# DIO_RJ45.net
KiCad netlist of a schematic drawn in Altium Designer
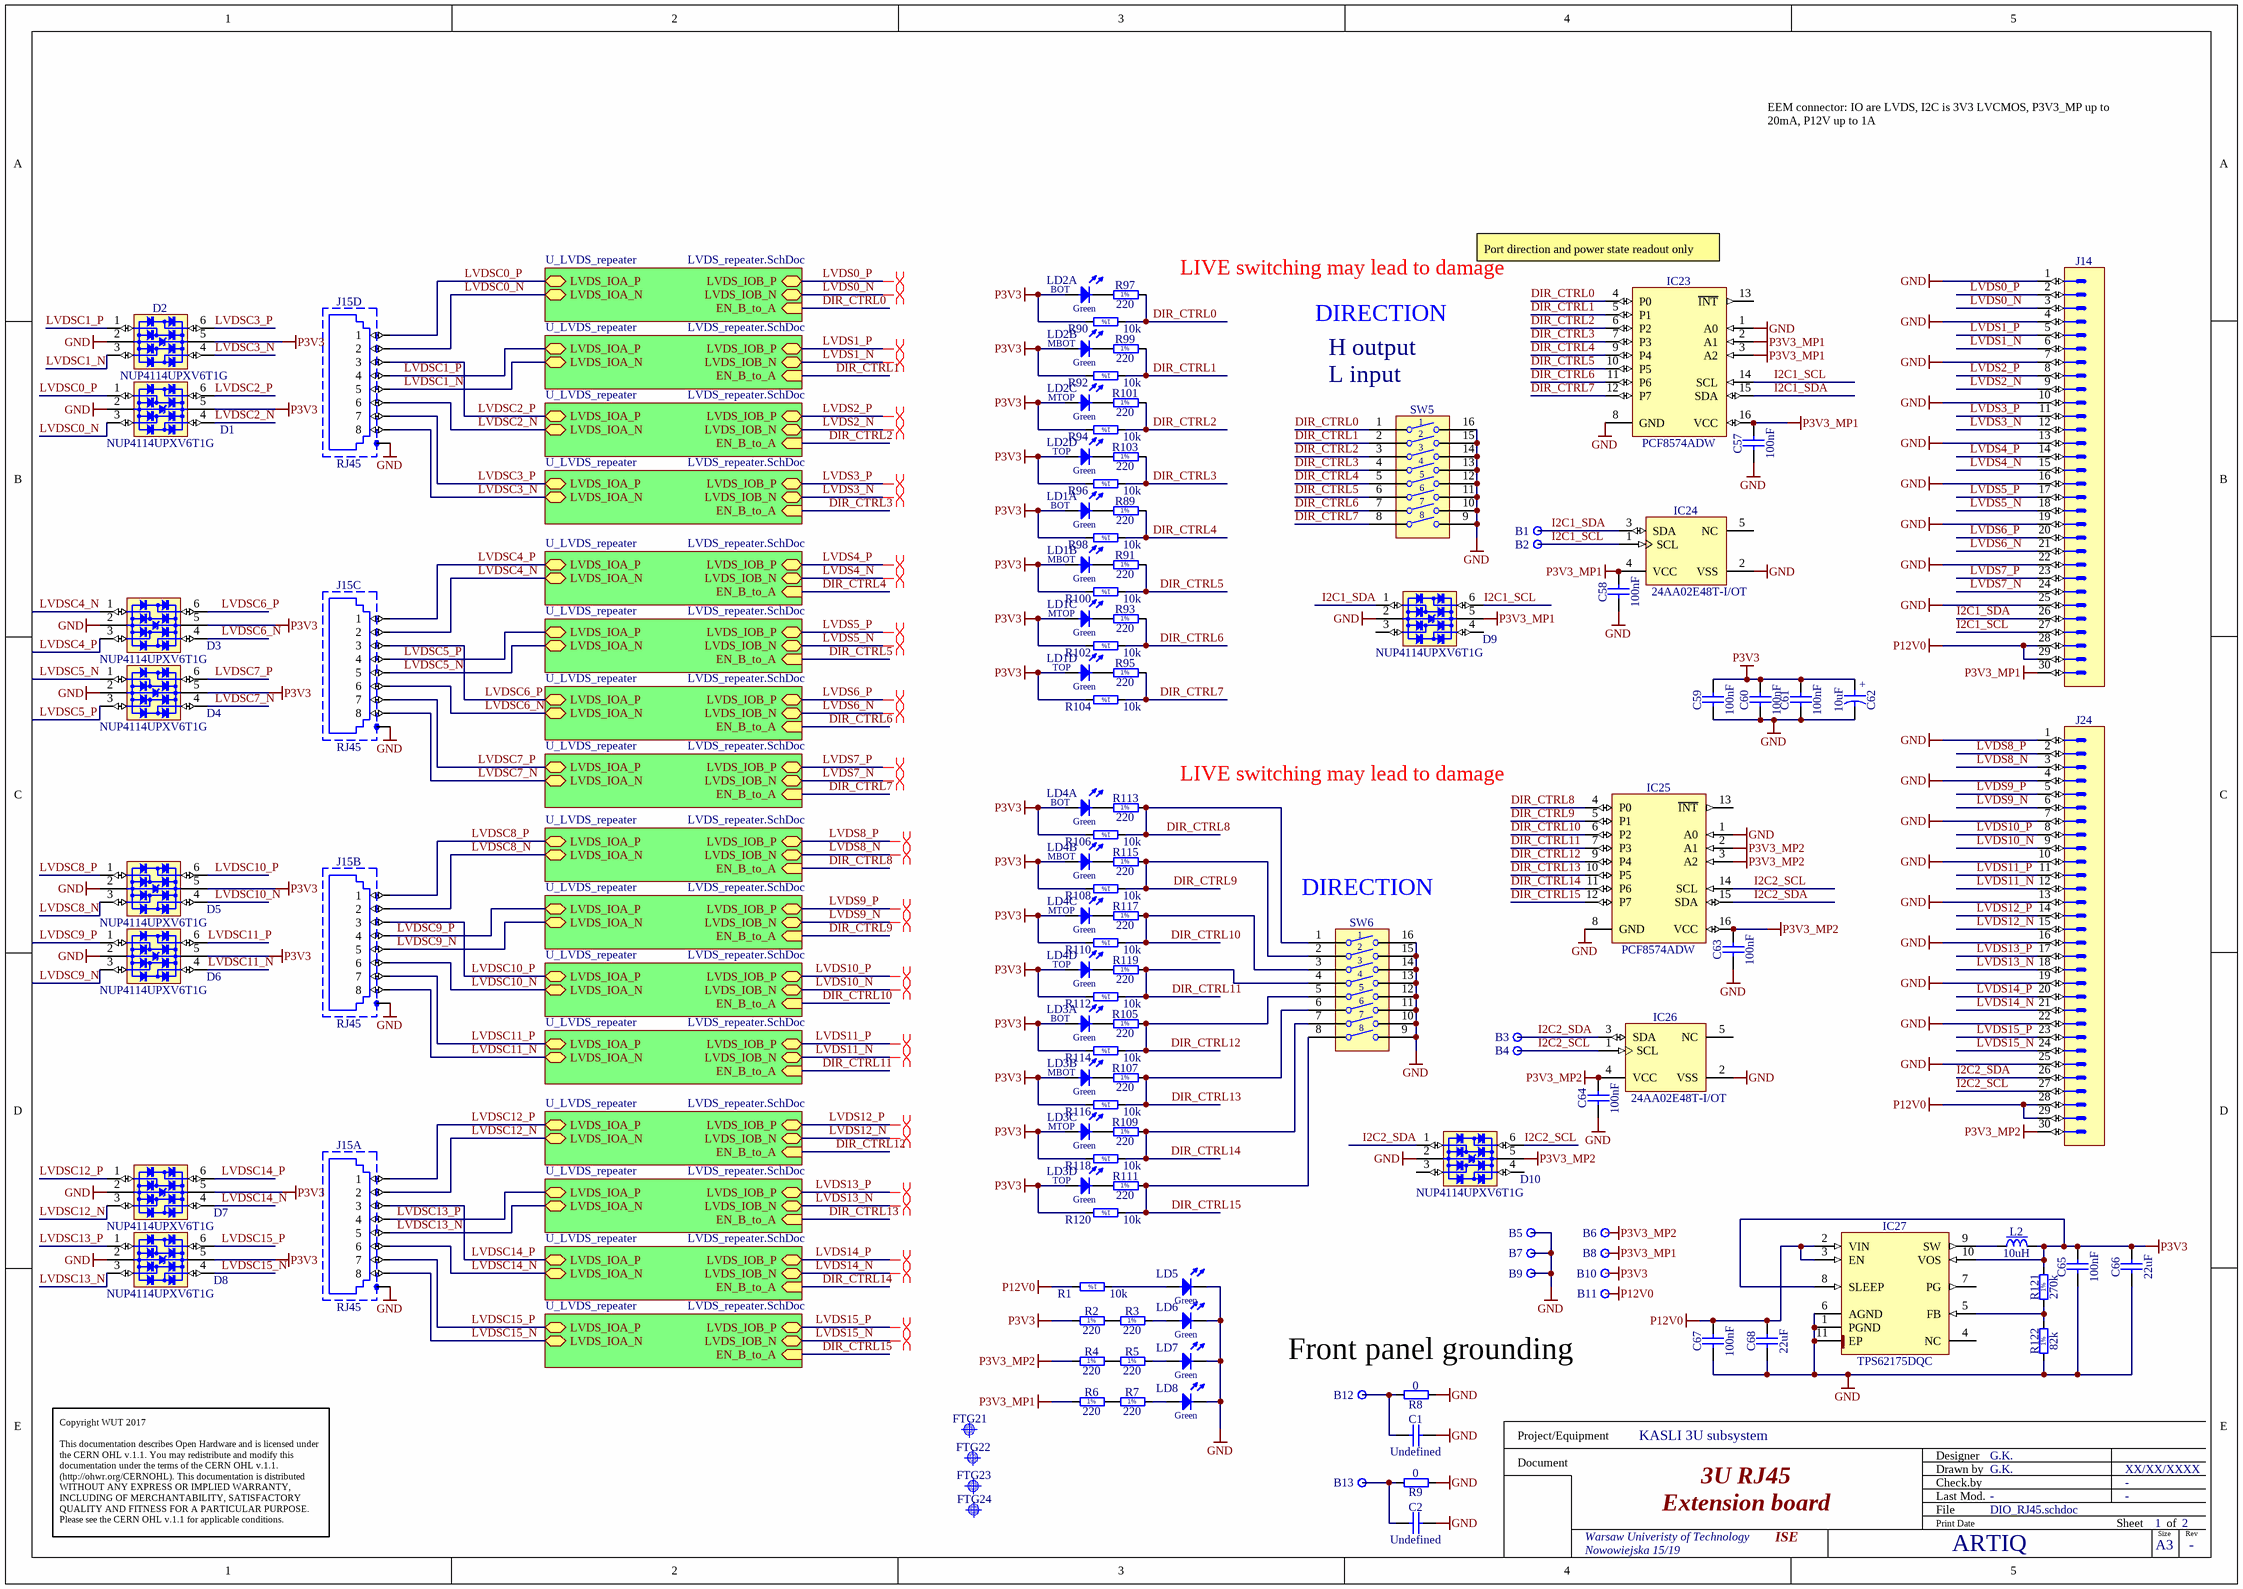
[diagram p0: DIO_RJ45.schdoc]

(export (version "E")
  (design (tool "Eeschema 10.0.6"))
  (components
    (comp (ref "B1")
      (value "Plated Hole")
      (footprint "c130h60")
      (description "Single Terminal Socket")
      (fields (field (name "PART NUMBER") "PLATED_HOLE0.6_PAD1.3") (field (name "AUTHOR") "CERN DEM MR"))
      (libsource (lib "Eletro-mechanical") (part "Single Terminal Socket"))
    )
    (comp (ref "B2")
      (value "Plated Hole")
      (footprint "c130h60")
      (description "Single Terminal Socket")
      (fields (field (name "PART NUMBER") "PLATED_HOLE0.6_PAD1.3") (field (name "AUTHOR") "CERN DEM MR"))
      (libsource (lib "Eletro-mechanical") (part "Single Terminal Socket"))
    )
    (comp (ref "B3")
      (value "Plated Hole")
      (footprint "c130h60")
      (description "Single Terminal Socket")
      (fields (field (name "PART NUMBER") "PLATED_HOLE0.6_PAD1.3") (field (name "AUTHOR") "CERN DEM MR"))
      (libsource (lib "Eletro-mechanical") (part "Single Terminal Socket"))
    )
    (comp (ref "B4")
      (value "Plated Hole")
      (footprint "c130h60")
      (description "Single Terminal Socket")
      (fields (field (name "PART NUMBER") "PLATED_HOLE0.6_PAD1.3") (field (name "AUTHOR") "CERN DEM MR"))
      (libsource (lib "Eletro-mechanical") (part "Single Terminal Socket"))
    )
    (comp (ref "B5")
      (value "Plated Hole")
      (footprint "c130h60")
      (description "Single Terminal Socket")
      (fields (field (name "PART NUMBER") "PLATED_HOLE0.6_PAD1.3") (field (name "AUTHOR") "CERN DEM MR"))
      (libsource (lib "Eletro-mechanical") (part "Single Terminal Socket"))
    )
    (comp (ref "B6")
      (value "Plated Hole")
      (footprint "c130h60")
      (description "Single Terminal Socket")
      (fields (field (name "PART NUMBER") "PLATED_HOLE0.6_PAD1.3") (field (name "AUTHOR") "CERN DEM MR"))
      (libsource (lib "Eletro-mechanical") (part "Single Terminal Socket"))
    )
    (comp (ref "B7")
      (value "Plated Hole")
      (footprint "c130h60")
      (description "Single Terminal Socket")
      (fields (field (name "PART NUMBER") "PLATED_HOLE0.6_PAD1.3") (field (name "AUTHOR") "CERN DEM MR"))
      (libsource (lib "Eletro-mechanical") (part "Single Terminal Socket"))
    )
    (comp (ref "B8")
      (value "Plated Hole")
      (footprint "c130h60")
      (description "Single Terminal Socket")
      (fields (field (name "PART NUMBER") "PLATED_HOLE0.6_PAD1.3") (field (name "AUTHOR") "CERN DEM MR"))
      (libsource (lib "Eletro-mechanical") (part "Single Terminal Socket"))
    )
    (comp (ref "B9")
      (value "Plated Hole")
      (footprint "c130h60")
      (description "Single Terminal Socket")
      (fields (field (name "PART NUMBER") "PLATED_HOLE0.6_PAD1.3") (field (name "AUTHOR") "CERN DEM MR"))
      (libsource (lib "Eletro-mechanical") (part "Single Terminal Socket"))
    )
    (comp (ref "B10")
      (value "Plated Hole")
      (footprint "c130h60")
      (description "Single Terminal Socket")
      (fields (field (name "PART NUMBER") "PLATED_HOLE0.6_PAD1.3") (field (name "AUTHOR") "CERN DEM MR"))
      (libsource (lib "Eletro-mechanical") (part "Single Terminal Socket"))
    )
    (comp (ref "B11")
      (value "Plated Hole")
      (footprint "c130h60")
      (description "Single Terminal Socket")
      (fields (field (name "PART NUMBER") "PLATED_HOLE0.6_PAD1.3") (field (name "AUTHOR") "CERN DEM MR"))
      (libsource (lib "Eletro-mechanical") (part "Single Terminal Socket"))
    )
    (comp (ref "B12")
      (value "Plated Hole")
      (footprint "MTG270_500")
      (description "Single Terminal Socket")
      (fields (field (name "PART NUMBER") "PLATED_HOLE2.7_PAD5.0") (field (name "AUTHOR") "CERN DEM JMW"))
      (libsource (lib "Eletro-mechanical") (part "Single Terminal Socket"))
    )
    (comp (ref "B13")
      (value "Plated Hole")
      (footprint "MTG270_500")
      (description "Single Terminal Socket")
      (fields (field (name "PART NUMBER") "PLATED_HOLE2.7_PAD5.0") (field (name "AUTHOR") "CERN DEM JMW"))
      (libsource (lib "Eletro-mechanical") (part "Single Terminal Socket"))
    )
    (comp (ref "C1")
      (value "Undefined")
      (footprint "CAPC2012X135N")
      (description "Non-polarised capacitor")
      (fields (field (name "PART NUMBER") "CC0805_NO-VALUE") (field (name "AUTHOR") "CERN DEM JLC"))
      (libsource (lib "Capacitors") (part "Capacitor - non polarized"))
    )
    (comp (ref "C2")
      (value "Undefined")
      (footprint "CAPC2012X135N")
      (description "Non-polarised capacitor")
      (fields (field (name "PART NUMBER") "CC0805_NO-VALUE") (field (name "AUTHOR") "CERN DEM JLC"))
      (libsource (lib "Capacitors") (part "Capacitor - non polarized"))
    )
    (comp (ref "C57")
      (value "100nF")
      (footprint "CAPC1005X55N")
      (description "Non-polarised capacitor")
      (fields
        (field (name "PART NUMBER") "CC0402_100NF_16V_10%_X5R")
        (field (name "VOLTAGE") "16V")
        (field (name "AUTHOR") "CERN DEM JLC")
      )
      (libsource (lib "Capacitors") (part "Capacitor - non polarized"))
    )
    (comp (ref "C58")
      (value "100nF")
      (footprint "CAPC1005X55N")
      (description "Non-polarised capacitor")
      (fields
        (field (name "PART NUMBER") "CC0402_100NF_16V_10%_X5R")
        (field (name "VOLTAGE") "16V")
        (field (name "AUTHOR") "CERN DEM JLC")
      )
      (libsource (lib "Capacitors") (part "Capacitor - non polarized"))
    )
    (comp (ref "C59")
      (value "100nF")
      (footprint "CAPC1005X55N")
      (description "Non-polarised capacitor")
      (fields
        (field (name "PART NUMBER") "CC0402_100NF_16V_10%_X5R")
        (field (name "VOLTAGE") "16V")
        (field (name "AUTHOR") "CERN DEM JLC")
      )
      (libsource (lib "Capacitors") (part "Capacitor - non polarized"))
    )
    (comp (ref "C60")
      (value "100nF")
      (footprint "CAPC1005X55N")
      (description "Non-polarised capacitor")
      (fields
        (field (name "PART NUMBER") "CC0402_100NF_16V_10%_X5R")
        (field (name "VOLTAGE") "16V")
        (field (name "AUTHOR") "CERN DEM JLC")
      )
      (libsource (lib "Capacitors") (part "Capacitor - non polarized"))
    )
    (comp (ref "C61")
      (value "100nF")
      (footprint "CAPC1005X55N")
      (description "Non-polarised capacitor")
      (fields
        (field (name "PART NUMBER") "CC0402_100NF_16V_10%_X5R")
        (field (name "VOLTAGE") "16V")
        (field (name "AUTHOR") "CERN DEM JLC")
      )
      (libsource (lib "Capacitors") (part "Capacitor - non polarized"))
    )
    (comp (ref "C62")
      (value "10uF")
      (footprint "CAPAE430X540N")
      (description "Polarised capacitor")
      (fields
        (field (name "PART NUMBER") "CAE430-540_10UF_16V_20%")
        (field (name "VOLTAGE") "16V")
        (field (name "AUTHOR") "CERN DEM JLC")
      )
      (libsource (lib "Capacitors") (part "Capacitor - polarized"))
    )
    (comp (ref "C63")
      (value "100nF")
      (footprint "CAPC1005X55N")
      (description "Non-polarised capacitor")
      (fields
        (field (name "PART NUMBER") "CC0402_100NF_16V_10%_X5R")
        (field (name "VOLTAGE") "16V")
        (field (name "AUTHOR") "CERN DEM JLC")
      )
      (libsource (lib "Capacitors") (part "Capacitor - non polarized"))
    )
    (comp (ref "C64")
      (value "100nF")
      (footprint "CAPC1005X55N")
      (description "Non-polarised capacitor")
      (fields
        (field (name "PART NUMBER") "CC0402_100NF_16V_10%_X5R")
        (field (name "VOLTAGE") "16V")
        (field (name "AUTHOR") "CERN DEM JLC")
      )
      (libsource (lib "Capacitors") (part "Capacitor - non polarized"))
    )
    (comp (ref "C65")
      (value "100nF")
      (footprint "CAPC1005X55N")
      (description "Non-polarised capacitor")
      (fields
        (field (name "PART NUMBER") "CC0402_100NF_16V_10%_X5R")
        (field (name "VOLTAGE") "16V")
        (field (name "AUTHOR") "CERN DEM JLC")
      )
      (libsource (lib "Capacitors") (part "Capacitor - non polarized"))
    )
    (comp (ref "C66")
      (value "22uF")
      (footprint "CAPC2012X135N")
      (description "Non-polarised capacitor")
      (fields
        (field (name "PART NUMBER") "CC0805_22UF_16V_10%_X5R")
        (field (name "VOLTAGE") "16V")
        (field (name "AUTHOR") "CERN DEM JLC")
      )
      (libsource (lib "Capacitors") (part "Capacitor - non polarized"))
    )
    (comp (ref "C67")
      (value "100nF")
      (footprint "CAPC1005X55N")
      (description "Non-polarised capacitor")
      (fields
        (field (name "PART NUMBER") "CC0402_100NF_16V_10%_X5R")
        (field (name "VOLTAGE") "16V")
        (field (name "AUTHOR") "CERN DEM JLC")
      )
      (libsource (lib "Capacitors") (part "Capacitor - non polarized"))
    )
    (comp (ref "C68")
      (value "22uF")
      (footprint "CAPC2012X135N")
      (description "Non-polarised capacitor")
      (fields
        (field (name "PART NUMBER") "CC0805_22UF_16V_10%_X5R")
        (field (name "VOLTAGE") "16V")
        (field (name "AUTHOR") "CERN DEM JLC")
      )
      (libsource (lib "Capacitors") (part "Capacitor - non polarized"))
    )
    (comp (ref "D1")
      (value "NUP4114UPXV6T1G")
      (footprint "SOTFL50P160X60-6N")
      (fields
        (field (name "VOLTAGE") "5.5V")
        (field (name "MANUFACTURER") "ON SEMICONDUCTOR")
        (field (name "AUTHOR") "CERN DEM JLC")
      )
      (libsource (lib "ICs And Semiconductors") (part "NUP4114"))
    )
    (comp (ref "D2")
      (value "NUP4114UPXV6T1G")
      (footprint "SOTFL50P160X60-6N")
      (fields
        (field (name "VOLTAGE") "5.5V")
        (field (name "MANUFACTURER") "ON SEMICONDUCTOR")
        (field (name "AUTHOR") "CERN DEM JLC")
      )
      (libsource (lib "ICs And Semiconductors") (part "NUP4114"))
    )
    (comp (ref "D3")
      (value "NUP4114UPXV6T1G")
      (footprint "SOTFL50P160X60-6N")
      (fields
        (field (name "VOLTAGE") "5.5V")
        (field (name "MANUFACTURER") "ON SEMICONDUCTOR")
        (field (name "AUTHOR") "CERN DEM JLC")
      )
      (libsource (lib "ICs And Semiconductors") (part "NUP4114"))
    )
    (comp (ref "D4")
      (value "NUP4114UPXV6T1G")
      (footprint "SOTFL50P160X60-6N")
      (fields
        (field (name "VOLTAGE") "5.5V")
        (field (name "MANUFACTURER") "ON SEMICONDUCTOR")
        (field (name "AUTHOR") "CERN DEM JLC")
      )
      (libsource (lib "ICs And Semiconductors") (part "NUP4114"))
    )
    (comp (ref "D5")
      (value "NUP4114UPXV6T1G")
      (footprint "SOTFL50P160X60-6N")
      (fields
        (field (name "VOLTAGE") "5.5V")
        (field (name "MANUFACTURER") "ON SEMICONDUCTOR")
        (field (name "AUTHOR") "CERN DEM JLC")
      )
      (libsource (lib "ICs And Semiconductors") (part "NUP4114"))
    )
    (comp (ref "D6")
      (value "NUP4114UPXV6T1G")
      (footprint "SOTFL50P160X60-6N")
      (fields
        (field (name "VOLTAGE") "5.5V")
        (field (name "MANUFACTURER") "ON SEMICONDUCTOR")
        (field (name "AUTHOR") "CERN DEM JLC")
      )
      (libsource (lib "ICs And Semiconductors") (part "NUP4114"))
    )
    (comp (ref "D7")
      (value "NUP4114UPXV6T1G")
      (footprint "SOTFL50P160X60-6N")
      (fields
        (field (name "VOLTAGE") "5.5V")
        (field (name "MANUFACTURER") "ON SEMICONDUCTOR")
        (field (name "AUTHOR") "CERN DEM JLC")
      )
      (libsource (lib "ICs And Semiconductors") (part "NUP4114"))
    )
    (comp (ref "D8")
      (value "NUP4114UPXV6T1G")
      (footprint "SOTFL50P160X60-6N")
      (fields
        (field (name "VOLTAGE") "5.5V")
        (field (name "MANUFACTURER") "ON SEMICONDUCTOR")
        (field (name "AUTHOR") "CERN DEM JLC")
      )
      (libsource (lib "ICs And Semiconductors") (part "NUP4114"))
    )
    (comp (ref "D9")
      (value "NUP4114UPXV6T1G")
      (footprint "SOTFL50P160X60-6N")
      (fields
        (field (name "VOLTAGE") "5.5V")
        (field (name "MANUFACTURER") "ON SEMICONDUCTOR")
        (field (name "AUTHOR") "CERN DEM JLC")
      )
      (libsource (lib "ICs And Semiconductors") (part "NUP4114"))
    )
    (comp (ref "D10")
      (value "NUP4114UPXV6T1G")
      (footprint "SOTFL50P160X60-6N")
      (fields
        (field (name "VOLTAGE") "5.5V")
        (field (name "MANUFACTURER") "ON SEMICONDUCTOR")
        (field (name "AUTHOR") "CERN DEM JLC")
      )
      (libsource (lib "ICs And Semiconductors") (part "NUP4114"))
    )
    (comp (ref "FTG21")
      (value "Use only in PCB")
      (footprint "FIDUCIAL_TOP_C100-200")
      (description "Fiducial Target")
      (fields (field (name "PART NUMBER") "FIDUCIAL_TARGET_C100-200") (field (name "AUTHOR") "CERN DEM JLC"))
      (libsource (lib "Eletro-mechanical") (part "Fiducial Target"))
    )
    (comp (ref "FTG22")
      (value "Use only in PCB")
      (footprint "FIDUCIAL_TOP_S100-200")
      (description "Fiducial Target")
      (fields (field (name "PART NUMBER") "FIDUCIAL_TARGET_S100-200") (field (name "AUTHOR") "CERN DEM JLC"))
      (libsource (lib "Eletro-mechanical") (part "Fiducial Target"))
    )
    (comp (ref "FTG23")
      (value "Use only in PCB")
      (footprint "FIDUCIAL_TOP_S200-400")
      (description "Fiducial Target")
      (fields (field (name "PART NUMBER") "FIDUCIAL_TARGET_S200-400") (field (name "AUTHOR") "CERN DEM JLC"))
      (libsource (lib "Eletro-mechanical") (part "Fiducial Target"))
    )
    (comp (ref "FTG24")
      (value "Use only in PCB")
      (footprint "FIDUCIAL_TOP_S100-200")
      (description "Fiducial Target")
      (fields (field (name "PART NUMBER") "FIDUCIAL_TARGET_S100-200") (field (name "AUTHOR") "CERN DEM JLC"))
      (libsource (lib "Eletro-mechanical") (part "Fiducial Target"))
    )
    (comp (ref "IC23")
      (value "PCF8574ADW")
      (footprint "SOIC127P1030X265-16N")
      (description "Remote 8-bit I/O Expander For I2C Bus")
      (fields (field (name "MANUFACTURER") "TEXAS INSTRUMENTS") (field (name "AUTHOR") "CERN DEM JLC"))
      (libsource (lib "ICs And Semiconductors") (part "PCF8574ADW"))
    )
    (comp (ref "IC24")
      (value "24AA02E48T-I/OT")
      (footprint "SOT95P280X145-5N")
      (description "1.7V-5.5V, 2K I2C Serial EEPROM With EUI-48 Node Identity")
      (fields (field (name "MANUFACTURER") "MICROCHIP TECHNOLOGY") (field (name "AUTHOR") "CERN DEM MR"))
      (libsource (lib "ICs And Semiconductors") (part "24AA02E48T-I/OT"))
    )
    (comp (ref "IC25")
      (value "PCF8574ADW")
      (footprint "SOIC127P1030X265-16N")
      (description "Remote 8-bit I/O Expander For I2C Bus")
      (fields (field (name "MANUFACTURER") "TEXAS INSTRUMENTS") (field (name "AUTHOR") "CERN DEM JLC"))
      (libsource (lib "ICs And Semiconductors") (part "PCF8574ADW"))
    )
    (comp (ref "IC26")
      (value "24AA02E48T-I/OT")
      (footprint "SOT95P280X145-5N")
      (description "1.7V-5.5V, 2K I2C Serial EEPROM With EUI-48 Node Identity")
      (fields (field (name "MANUFACTURER") "MICROCHIP TECHNOLOGY") (field (name "AUTHOR") "CERN DEM MR"))
      (libsource (lib "ICs And Semiconductors") (part "24AA02E48T-I/OT"))
    )
    (comp (ref "IC27")
      (value "TPS62175DQC")
      (footprint "SON50P200X300X80-11N-R94X250")
      (description "4.75-28VDC to 1-6VDC, 500mA Step-Down Converter With Sleep Mode")
      (fields (field (name "MANUFACTURER") "TEXAS INSTRUMENTS") (field (name "AUTHOR") "CERN DEM JMW"))
      (libsource (lib "ICs And Semiconductors") (part "TPS62175"))
    )
    (comp (ref "J14")
      (value "~")
      (footprint "3M_N2530-6002RB")
      (description "Connector 30 Male")
      (fields
        (field (name "PART NUMBER") "3M_N2530-6002RB")
        (field (name "MANUFACTURER") "3M")
        (field (name "AUTHOR") "CERN DEM JLC")
      )
      (libsource (lib "Connectors") (part "Connector 30 Male"))
    )
    (comp (ref "J15")
      (value "RJ45")
      (footprint "TYCO_5406203-3")
      (description "Connector 4 x RJ45 + Shield")
      (fields
        (field (name "PART NUMBER") "TYCO_5406203-3")
        (field (name "MANUFACTURER") "TYCO ELECTRONICS")
        (field (name "AUTHOR") "CERN DEM JLC")
      )
      (libsource (lib "Connectors") (part "Connector 4 x RJ45 + Shield"))
    )
    (comp (ref "J24")
      (value "~")
      (footprint "3M_N2530-6002RB")
      (description "Connector 30 Male")
      (fields
        (field (name "PART NUMBER") "3M_N2530-6002RB")
        (field (name "MANUFACTURER") "3M")
        (field (name "AUTHOR") "CERN DEM JLC")
      )
      (libsource (lib "Connectors") (part "Connector 30 Male"))
    )
    (comp (ref "L2")
      (value "10uH")
      (footprint "IND_MURATA-PS_8400")
      (description "Inductor With Core")
      (fields
        (field (name "PART NUMBER") "IND_10UH_10%_MURATA-PS_8400")
        (field (name "POWER") "950mA")
        (field (name "AUTHOR") "CERN DEM JLC")
      )
      (libsource (lib "Inductors & Transformers") (part "Inductor With Magnetic core"))
    )
    (comp (ref "LD1")
      (value "Green")
      (footprint "LED_BIVAR_H485CGDL")
      (description "LED x4 Green 1C2A-BOT_3C4A_5C6A_7C8A-TOP")
      (fields
        (field (name "PART NUMBER") "LED_BIVAR_H485CGDL")
        (field (name "MANUFACTURER") "BIVAR")
        (field (name "AUTHOR") "CERN DEM JLC")
      )
      (libsource (lib "ICs And Semiconductors") (part "LED x4 Green 1C2A-BOT_3C4A_5C6A_7C8A-TOP"))
    )
    (comp (ref "LD2")
      (value "Green")
      (footprint "LED_BIVAR_H485CGDL")
      (description "LED x4 Green 1C2A-BOT_3C4A_5C6A_7C8A-TOP")
      (fields
        (field (name "PART NUMBER") "LED_BIVAR_H485CGDL")
        (field (name "MANUFACTURER") "BIVAR")
        (field (name "AUTHOR") "CERN DEM JLC")
      )
      (libsource (lib "ICs And Semiconductors") (part "LED x4 Green 1C2A-BOT_3C4A_5C6A_7C8A-TOP"))
    )
    (comp (ref "LD3")
      (value "Green")
      (footprint "LED_BIVAR_H485CGDL")
      (description "LED x4 Green 1C2A-BOT_3C4A_5C6A_7C8A-TOP")
      (fields
        (field (name "PART NUMBER") "LED_BIVAR_H485CGDL")
        (field (name "MANUFACTURER") "BIVAR")
        (field (name "AUTHOR") "CERN DEM JLC")
      )
      (libsource (lib "ICs And Semiconductors") (part "LED x4 Green 1C2A-BOT_3C4A_5C6A_7C8A-TOP"))
    )
    (comp (ref "LD4")
      (value "Green")
      (footprint "LED_BIVAR_H485CGDL")
      (description "LED x4 Green 1C2A-BOT_3C4A_5C6A_7C8A-TOP")
      (fields
        (field (name "PART NUMBER") "LED_BIVAR_H485CGDL")
        (field (name "MANUFACTURER") "BIVAR")
        (field (name "AUTHOR") "CERN DEM JLC")
      )
      (libsource (lib "ICs And Semiconductors") (part "LED x4 Green 1C2A-BOT_3C4A_5C6A_7C8A-TOP"))
    )
    (comp (ref "LD5")
      (value "Green")
      (footprint "LED_KINGBRIGHT_KPH-1608CGCK")
      (description "LED Green 1C 2A")
      (fields
        (field (name "PART NUMBER") "LED_KINGBRIGHT_KPH-1608CGCK")
        (field (name "MANUFACTURER") "KINGBRIGHT")
        (field (name "AUTHOR") "CERN DEM JLC")
      )
      (libsource (lib "ICs And Semiconductors") (part "LED Green 1C 2A"))
    )
    (comp (ref "LD6")
      (value "Green")
      (footprint "LED_KINGBRIGHT_KPH-1608CGCK")
      (description "LED Green 1C 2A")
      (fields
        (field (name "PART NUMBER") "LED_KINGBRIGHT_KPH-1608CGCK")
        (field (name "MANUFACTURER") "KINGBRIGHT")
        (field (name "AUTHOR") "CERN DEM JLC")
      )
      (libsource (lib "ICs And Semiconductors") (part "LED Green 1C 2A"))
    )
    (comp (ref "LD7")
      (value "Green")
      (footprint "LED_KINGBRIGHT_KPH-1608CGCK")
      (description "LED Green 1C 2A")
      (fields
        (field (name "PART NUMBER") "LED_KINGBRIGHT_KPH-1608CGCK")
        (field (name "MANUFACTURER") "KINGBRIGHT")
        (field (name "AUTHOR") "CERN DEM JLC")
      )
      (libsource (lib "ICs And Semiconductors") (part "LED Green 1C 2A"))
    )
    (comp (ref "LD8")
      (value "Green")
      (footprint "LED_KINGBRIGHT_KPH-1608CGCK")
      (description "LED Green 1C 2A")
      (fields
        (field (name "PART NUMBER") "LED_KINGBRIGHT_KPH-1608CGCK")
        (field (name "MANUFACTURER") "KINGBRIGHT")
        (field (name "AUTHOR") "CERN DEM JLC")
      )
      (libsource (lib "ICs And Semiconductors") (part "LED Green 1C 2A"))
    )
    (comp (ref "R1")
      (value "10k")
      (footprint "RESC1005X40N")
      (description "Resistor - 1%")
      (fields
        (field (name "PART NUMBER") "R0402_10K_1%_0.0625W_100PPM")
        (field (name "POWER") "0.0625W")
        (field (name "AUTHOR") "CERN DEM JLC")
      )
      (libsource (lib "Resistors") (part "Resistor - 1%"))
    )
    (comp (ref "R2")
      (value "220")
      (footprint "RESC1608X55N")
      (description "Resistor - 1%")
      (fields
        (field (name "PART NUMBER") "R0603_220R_1%_0.1W_100PPM")
        (field (name "POWER") "0.1W")
        (field (name "AUTHOR") "CERN DEM JLC")
      )
      (libsource (lib "Resistors") (part "Resistor - 1%"))
    )
    (comp (ref "R3")
      (value "220")
      (footprint "RESC1608X55N")
      (description "Resistor - 1%")
      (fields
        (field (name "PART NUMBER") "R0603_220R_1%_0.1W_100PPM")
        (field (name "POWER") "0.1W")
        (field (name "AUTHOR") "CERN DEM JLC")
      )
      (libsource (lib "Resistors") (part "Resistor - 1%"))
    )
    (comp (ref "R4")
      (value "220")
      (footprint "RESC1608X55N")
      (description "Resistor - 1%")
      (fields
        (field (name "PART NUMBER") "R0603_220R_1%_0.1W_100PPM")
        (field (name "POWER") "0.1W")
        (field (name "AUTHOR") "CERN DEM JLC")
      )
      (libsource (lib "Resistors") (part "Resistor - 1%"))
    )
    (comp (ref "R5")
      (value "220")
      (footprint "RESC1608X55N")
      (description "Resistor - 1%")
      (fields
        (field (name "PART NUMBER") "R0603_220R_1%_0.1W_100PPM")
        (field (name "POWER") "0.1W")
        (field (name "AUTHOR") "CERN DEM JLC")
      )
      (libsource (lib "Resistors") (part "Resistor - 1%"))
    )
    (comp (ref "R6")
      (value "220")
      (footprint "RESC1608X55N")
      (description "Resistor - 1%")
      (fields
        (field (name "PART NUMBER") "R0603_220R_1%_0.1W_100PPM")
        (field (name "POWER") "0.1W")
        (field (name "AUTHOR") "CERN DEM JLC")
      )
      (libsource (lib "Resistors") (part "Resistor - 1%"))
    )
    (comp (ref "R7")
      (value "220")
      (footprint "RESC1608X55N")
      (description "Resistor - 1%")
      (fields
        (field (name "PART NUMBER") "R0603_220R_1%_0.1W_100PPM")
        (field (name "POWER") "0.1W")
        (field (name "AUTHOR") "CERN DEM JLC")
      )
      (libsource (lib "Resistors") (part "Resistor - 1%"))
    )
    (comp (ref "R8")
      (value "0")
      (footprint "RESC1608X55N")
      (description "Resistor")
      (fields
        (field (name "PART NUMBER") "R0603_0R_JUMPER")
        (field (name "MANUFACTURER") "GENERIC")
        (field (name "AUTHOR") "CERN DEM JLC")
      )
      (libsource (lib "Resistors") (part "Resistor"))
    )
    (comp (ref "R9")
      (value "0")
      (footprint "RESC1608X55N")
      (description "Resistor")
      (fields
        (field (name "PART NUMBER") "R0603_0R_JUMPER")
        (field (name "MANUFACTURER") "GENERIC")
        (field (name "AUTHOR") "CERN DEM JLC")
      )
      (libsource (lib "Resistors") (part "Resistor"))
    )
    (comp (ref "R89")
      (value "220")
      (footprint "RESC1608X55N")
      (description "Resistor - 1%")
      (fields
        (field (name "PART NUMBER") "R0603_220R_1%_0.1W_100PPM")
        (field (name "POWER") "0.1W")
        (field (name "AUTHOR") "CERN DEM JLC")
      )
      (libsource (lib "Resistors") (part "Resistor - 1%"))
    )
    (comp (ref "R90")
      (value "10k")
      (footprint "RESC1005X40N")
      (description "Resistor - 1%")
      (fields
        (field (name "PART NUMBER") "R0402_10K_1%_0.0625W_100PPM")
        (field (name "POWER") "0.0625W")
        (field (name "AUTHOR") "CERN DEM JLC")
      )
      (libsource (lib "Resistors") (part "Resistor - 1%"))
    )
    (comp (ref "R91")
      (value "220")
      (footprint "RESC1608X55N")
      (description "Resistor - 1%")
      (fields
        (field (name "PART NUMBER") "R0603_220R_1%_0.1W_100PPM")
        (field (name "POWER") "0.1W")
        (field (name "AUTHOR") "CERN DEM JLC")
      )
      (libsource (lib "Resistors") (part "Resistor - 1%"))
    )
    (comp (ref "R92")
      (value "10k")
      (footprint "RESC1005X40N")
      (description "Resistor - 1%")
      (fields
        (field (name "PART NUMBER") "R0402_10K_1%_0.0625W_100PPM")
        (field (name "POWER") "0.0625W")
        (field (name "AUTHOR") "CERN DEM JLC")
      )
      (libsource (lib "Resistors") (part "Resistor - 1%"))
    )
    (comp (ref "R93")
      (value "220")
      (footprint "RESC1608X55N")
      (description "Resistor - 1%")
      (fields
        (field (name "PART NUMBER") "R0603_220R_1%_0.1W_100PPM")
        (field (name "POWER") "0.1W")
        (field (name "AUTHOR") "CERN DEM JLC")
      )
      (libsource (lib "Resistors") (part "Resistor - 1%"))
    )
    (comp (ref "R94")
      (value "10k")
      (footprint "RESC1005X40N")
      (description "Resistor - 1%")
      (fields
        (field (name "PART NUMBER") "R0402_10K_1%_0.0625W_100PPM")
        (field (name "POWER") "0.0625W")
        (field (name "AUTHOR") "CERN DEM JLC")
      )
      (libsource (lib "Resistors") (part "Resistor - 1%"))
    )
    (comp (ref "R95")
      (value "220")
      (footprint "RESC1608X55N")
      (description "Resistor - 1%")
      (fields
        (field (name "PART NUMBER") "R0603_220R_1%_0.1W_100PPM")
        (field (name "POWER") "0.1W")
        (field (name "AUTHOR") "CERN DEM JLC")
      )
      (libsource (lib "Resistors") (part "Resistor - 1%"))
    )
    (comp (ref "R96")
      (value "10k")
      (footprint "RESC1005X40N")
      (description "Resistor - 1%")
      (fields
        (field (name "PART NUMBER") "R0402_10K_1%_0.0625W_100PPM")
        (field (name "POWER") "0.0625W")
        (field (name "AUTHOR") "CERN DEM JLC")
      )
      (libsource (lib "Resistors") (part "Resistor - 1%"))
    )
    (comp (ref "R97")
      (value "220")
      (footprint "RESC1608X55N")
      (description "Resistor - 1%")
      (fields
        (field (name "PART NUMBER") "R0603_220R_1%_0.1W_100PPM")
        (field (name "POWER") "0.1W")
        (field (name "AUTHOR") "CERN DEM JLC")
      )
      (libsource (lib "Resistors") (part "Resistor - 1%"))
    )
    (comp (ref "R98")
      (value "10k")
      (footprint "RESC1005X40N")
      (description "Resistor - 1%")
      (fields
        (field (name "PART NUMBER") "R0402_10K_1%_0.0625W_100PPM")
        (field (name "POWER") "0.0625W")
        (field (name "AUTHOR") "CERN DEM JLC")
      )
      (libsource (lib "Resistors") (part "Resistor - 1%"))
    )
    (comp (ref "R99")
      (value "220")
      (footprint "RESC1608X55N")
      (description "Resistor - 1%")
      (fields
        (field (name "PART NUMBER") "R0603_220R_1%_0.1W_100PPM")
        (field (name "POWER") "0.1W")
        (field (name "AUTHOR") "CERN DEM JLC")
      )
      (libsource (lib "Resistors") (part "Resistor - 1%"))
    )
    (comp (ref "R100")
      (value "10k")
      (footprint "RESC1005X40N")
      (description "Resistor - 1%")
      (fields
        (field (name "PART NUMBER") "R0402_10K_1%_0.0625W_100PPM")
        (field (name "POWER") "0.0625W")
        (field (name "AUTHOR") "CERN DEM JLC")
      )
      (libsource (lib "Resistors") (part "Resistor - 1%"))
    )
    (comp (ref "R101")
      (value "220")
      (footprint "RESC1608X55N")
      (description "Resistor - 1%")
      (fields
        (field (name "PART NUMBER") "R0603_220R_1%_0.1W_100PPM")
        (field (name "POWER") "0.1W")
        (field (name "AUTHOR") "CERN DEM JLC")
      )
      (libsource (lib "Resistors") (part "Resistor - 1%"))
    )
    (comp (ref "R102")
      (value "10k")
      (footprint "RESC1005X40N")
      (description "Resistor - 1%")
      (fields
        (field (name "PART NUMBER") "R0402_10K_1%_0.0625W_100PPM")
        (field (name "POWER") "0.0625W")
        (field (name "AUTHOR") "CERN DEM JLC")
      )
      (libsource (lib "Resistors") (part "Resistor - 1%"))
    )
    (comp (ref "R103")
      (value "220")
      (footprint "RESC1608X55N")
      (description "Resistor - 1%")
      (fields
        (field (name "PART NUMBER") "R0603_220R_1%_0.1W_100PPM")
        (field (name "POWER") "0.1W")
        (field (name "AUTHOR") "CERN DEM JLC")
      )
      (libsource (lib "Resistors") (part "Resistor - 1%"))
    )
    (comp (ref "R104")
      (value "10k")
      (footprint "RESC1005X40N")
      (description "Resistor - 1%")
      (fields
        (field (name "PART NUMBER") "R0402_10K_1%_0.0625W_100PPM")
        (field (name "POWER") "0.0625W")
        (field (name "AUTHOR") "CERN DEM JLC")
      )
      (libsource (lib "Resistors") (part "Resistor - 1%"))
    )
    (comp (ref "R105")
      (value "220")
      (footprint "RESC1608X55N")
      (description "Resistor - 1%")
      (fields
        (field (name "PART NUMBER") "R0603_220R_1%_0.1W_100PPM")
        (field (name "POWER") "0.1W")
        (field (name "AUTHOR") "CERN DEM JLC")
      )
      (libsource (lib "Resistors") (part "Resistor - 1%"))
    )
    (comp (ref "R106")
      (value "10k")
      (footprint "RESC1005X40N")
      (description "Resistor - 1%")
      (fields
        (field (name "PART NUMBER") "R0402_10K_1%_0.0625W_100PPM")
        (field (name "POWER") "0.0625W")
        (field (name "AUTHOR") "CERN DEM JLC")
      )
      (libsource (lib "Resistors") (part "Resistor - 1%"))
    )
    (comp (ref "R107")
      (value "220")
      (footprint "RESC1608X55N")
      (description "Resistor - 1%")
      (fields
        (field (name "PART NUMBER") "R0603_220R_1%_0.1W_100PPM")
        (field (name "POWER") "0.1W")
        (field (name "AUTHOR") "CERN DEM JLC")
      )
      (libsource (lib "Resistors") (part "Resistor - 1%"))
    )
    (comp (ref "R108")
      (value "10k")
      (footprint "RESC1005X40N")
      (description "Resistor - 1%")
      (fields
        (field (name "PART NUMBER") "R0402_10K_1%_0.0625W_100PPM")
        (field (name "POWER") "0.0625W")
        (field (name "AUTHOR") "CERN DEM JLC")
      )
      (libsource (lib "Resistors") (part "Resistor - 1%"))
    )
    (comp (ref "R109")
      (value "220")
      (footprint "RESC1608X55N")
      (description "Resistor - 1%")
      (fields
        (field (name "PART NUMBER") "R0603_220R_1%_0.1W_100PPM")
        (field (name "POWER") "0.1W")
        (field (name "AUTHOR") "CERN DEM JLC")
      )
      (libsource (lib "Resistors") (part "Resistor - 1%"))
    )
    (comp (ref "R110")
      (value "10k")
      (footprint "RESC1005X40N")
      (description "Resistor - 1%")
      (fields
        (field (name "PART NUMBER") "R0402_10K_1%_0.0625W_100PPM")
        (field (name "POWER") "0.0625W")
        (field (name "AUTHOR") "CERN DEM JLC")
      )
      (libsource (lib "Resistors") (part "Resistor - 1%"))
    )
    (comp (ref "R111")
      (value "220")
      (footprint "RESC1608X55N")
      (description "Resistor - 1%")
      (fields
        (field (name "PART NUMBER") "R0603_220R_1%_0.1W_100PPM")
        (field (name "POWER") "0.1W")
        (field (name "AUTHOR") "CERN DEM JLC")
      )
      (libsource (lib "Resistors") (part "Resistor - 1%"))
    )
    (comp (ref "R112")
      (value "10k")
      (footprint "RESC1005X40N")
      (description "Resistor - 1%")
      (fields
        (field (name "PART NUMBER") "R0402_10K_1%_0.0625W_100PPM")
        (field (name "POWER") "0.0625W")
        (field (name "AUTHOR") "CERN DEM JLC")
      )
      (libsource (lib "Resistors") (part "Resistor - 1%"))
    )
    (comp (ref "R113")
      (value "220")
      (footprint "RESC1608X55N")
      (description "Resistor - 1%")
      (fields
        (field (name "PART NUMBER") "R0603_220R_1%_0.1W_100PPM")
        (field (name "POWER") "0.1W")
        (field (name "AUTHOR") "CERN DEM JLC")
      )
      (libsource (lib "Resistors") (part "Resistor - 1%"))
    )
    (comp (ref "R114")
      (value "10k")
      (footprint "RESC1005X40N")
      (description "Resistor - 1%")
      (fields
        (field (name "PART NUMBER") "R0402_10K_1%_0.0625W_100PPM")
        (field (name "POWER") "0.0625W")
        (field (name "AUTHOR") "CERN DEM JLC")
      )
      (libsource (lib "Resistors") (part "Resistor - 1%"))
    )
    (comp (ref "R115")
      (value "220")
      (footprint "RESC1608X55N")
      (description "Resistor - 1%")
      (fields
        (field (name "PART NUMBER") "R0603_220R_1%_0.1W_100PPM")
        (field (name "POWER") "0.1W")
        (field (name "AUTHOR") "CERN DEM JLC")
      )
      (libsource (lib "Resistors") (part "Resistor - 1%"))
    )
    (comp (ref "R116")
      (value "10k")
      (footprint "RESC1005X40N")
      (description "Resistor - 1%")
      (fields
        (field (name "PART NUMBER") "R0402_10K_1%_0.0625W_100PPM")
        (field (name "POWER") "0.0625W")
        (field (name "AUTHOR") "CERN DEM JLC")
      )
      (libsource (lib "Resistors") (part "Resistor - 1%"))
    )
    (comp (ref "R117")
      (value "220")
      (footprint "RESC1608X55N")
      (description "Resistor - 1%")
      (fields
        (field (name "PART NUMBER") "R0603_220R_1%_0.1W_100PPM")
        (field (name "POWER") "0.1W")
        (field (name "AUTHOR") "CERN DEM JLC")
      )
      (libsource (lib "Resistors") (part "Resistor - 1%"))
    )
    (comp (ref "R118")
      (value "10k")
      (footprint "RESC1005X40N")
      (description "Resistor - 1%")
      (fields
        (field (name "PART NUMBER") "R0402_10K_1%_0.0625W_100PPM")
        (field (name "POWER") "0.0625W")
        (field (name "AUTHOR") "CERN DEM JLC")
      )
      (libsource (lib "Resistors") (part "Resistor - 1%"))
    )
    (comp (ref "R119")
      (value "220")
      (footprint "RESC1608X55N")
      (description "Resistor - 1%")
      (fields
        (field (name "PART NUMBER") "R0603_220R_1%_0.1W_100PPM")
        (field (name "POWER") "0.1W")
        (field (name "AUTHOR") "CERN DEM JLC")
      )
      (libsource (lib "Resistors") (part "Resistor - 1%"))
    )
    (comp (ref "R120")
      (value "10k")
      (footprint "RESC1005X40N")
      (description "Resistor - 1%")
      (fields
        (field (name "PART NUMBER") "R0402_10K_1%_0.0625W_100PPM")
        (field (name "POWER") "0.0625W")
        (field (name "AUTHOR") "CERN DEM JLC")
      )
      (libsource (lib "Resistors") (part "Resistor - 1%"))
    )
    (comp (ref "R121")
      (value "270k")
      (footprint "RESC1608X55N")
      (description "Resistor - 1%")
      (fields
        (field (name "PART NUMBER") "R0603_270K_1%_0.1W_100PPM")
        (field (name "POWER") "0.1W")
        (field (name "AUTHOR") "CERN DEM JLC")
      )
      (libsource (lib "Resistors") (part "Resistor - 1%"))
    )
    (comp (ref "R122")
      (value "82k")
      (footprint "RESC1608X55N")
      (description "Resistor - 1%")
      (fields
        (field (name "PART NUMBER") "R0603_82K_1%_0.1W_100PPM")
        (field (name "POWER") "0.1W")
        (field (name "AUTHOR") "CERN DEM JLC")
      )
      (libsource (lib "Resistors") (part "Resistor - 1%"))
    )
    (comp (ref "SW5")
      (value "Switch")
      (footprint "SW_TYCO_1-1571983-0")
      (description "8 Ways SPST DIP Switch")
      (fields
        (field (name "PART NUMBER") "SW_TYCO_1-1571983-0")
        (field (name "MANUFACTURER") "TYCO")
        (field (name "AUTHOR") "CERN DEM JLC")
      )
      (libsource (lib "Eletro-mechanical") (part "SW 8x SPST DIP Switch"))
    )
    (comp (ref "SW6")
      (value "Switch")
      (footprint "SW_TYCO_1-1571983-0")
      (description "8 Ways SPST DIP Switch")
      (fields
        (field (name "PART NUMBER") "SW_TYCO_1-1571983-0")
        (field (name "MANUFACTURER") "TYCO")
        (field (name "AUTHOR") "CERN DEM JLC")
      )
      (libsource (lib "Eletro-mechanical") (part "SW 8x SPST DIP Switch"))
    )
  )
  (nets
    (net (code "1") (name "/DIR_CTRL0") (class "Default")
      (node (ref "IC23") (pin "4") (pinfunction "P0_4") (pintype "bidirectional"))
      (node (ref "R90") (pin "1") (pinfunction "1_1") (pintype "passive"))
      (node (ref "R97") (pin "2") (pinfunction "2_2") (pintype "passive"))
      (node (ref "SW5") (pin "1") (pinfunction "1_1") (pintype "passive"))
    )
    (net (code "2") (name "/DIR_CTRL1") (class "Default")
      (node (ref "IC23") (pin "5") (pinfunction "P1_5") (pintype "bidirectional"))
      (node (ref "R92") (pin "1") (pinfunction "1_1") (pintype "passive"))
      (node (ref "R99") (pin "2") (pinfunction "2_2") (pintype "passive"))
      (node (ref "SW5") (pin "2") (pinfunction "2_2") (pintype "passive"))
    )
    (net (code "3") (name "/DIR_CTRL2") (class "Default")
      (node (ref "IC23") (pin "6") (pinfunction "P2_6") (pintype "bidirectional"))
      (node (ref "R101") (pin "2") (pinfunction "2_2") (pintype "passive"))
      (node (ref "R94") (pin "1") (pinfunction "1_1") (pintype "passive"))
      (node (ref "SW5") (pin "3") (pinfunction "3_3") (pintype "passive"))
    )
    (net (code "4") (name "/DIR_CTRL3") (class "Default")
      (node (ref "IC23") (pin "7") (pinfunction "P3_7") (pintype "bidirectional"))
      (node (ref "R103") (pin "2") (pinfunction "2_2") (pintype "passive"))
      (node (ref "R96") (pin "1") (pinfunction "1_1") (pintype "passive"))
      (node (ref "SW5") (pin "4") (pinfunction "4_4") (pintype "passive"))
    )
    (net (code "5") (name "/DIR_CTRL4") (class "Default")
      (node (ref "IC23") (pin "9") (pinfunction "P4_9") (pintype "bidirectional"))
      (node (ref "R89") (pin "2") (pinfunction "2_2") (pintype "passive"))
      (node (ref "R98") (pin "1") (pinfunction "1_1") (pintype "passive"))
      (node (ref "SW5") (pin "5") (pinfunction "5_5") (pintype "passive"))
    )
    (net (code "6") (name "/DIR_CTRL5") (class "Default")
      (node (ref "IC23") (pin "10") (pinfunction "P5_10") (pintype "bidirectional"))
      (node (ref "R100") (pin "1") (pinfunction "1_1") (pintype "passive"))
      (node (ref "R91") (pin "2") (pinfunction "2_2") (pintype "passive"))
      (node (ref "SW5") (pin "6") (pinfunction "6_6") (pintype "passive"))
    )
    (net (code "7") (name "/DIR_CTRL6") (class "Default")
      (node (ref "IC23") (pin "11") (pinfunction "P6_11") (pintype "bidirectional"))
      (node (ref "R102") (pin "1") (pinfunction "1_1") (pintype "passive"))
      (node (ref "R93") (pin "2") (pinfunction "2_2") (pintype "passive"))
      (node (ref "SW5") (pin "7") (pinfunction "7_7") (pintype "passive"))
    )
    (net (code "8") (name "/DIR_CTRL7") (class "Default")
      (node (ref "IC23") (pin "12") (pinfunction "P7_12") (pintype "bidirectional"))
      (node (ref "R104") (pin "1") (pinfunction "1_1") (pintype "passive"))
      (node (ref "R95") (pin "2") (pinfunction "2_2") (pintype "passive"))
      (node (ref "SW5") (pin "8") (pinfunction "8_8") (pintype "passive"))
    )
    (net (code "9") (name "/DIR_CTRL8") (class "Default")
      (node (ref "IC25") (pin "4") (pinfunction "P0_4") (pintype "bidirectional"))
      (node (ref "R106") (pin "1") (pinfunction "1_1") (pintype "passive"))
      (node (ref "R113") (pin "2") (pinfunction "2_2") (pintype "passive"))
      (node (ref "SW6") (pin "1") (pinfunction "1_1") (pintype "passive"))
    )
    (net (code "10") (name "/DIR_CTRL9") (class "Default")
      (node (ref "IC25") (pin "5") (pinfunction "P1_5") (pintype "bidirectional"))
      (node (ref "R108") (pin "1") (pinfunction "1_1") (pintype "passive"))
      (node (ref "R115") (pin "2") (pinfunction "2_2") (pintype "passive"))
      (node (ref "SW6") (pin "2") (pinfunction "2_2") (pintype "passive"))
    )
    (net (code "11") (name "/DIR_CTRL10") (class "Default")
      (node (ref "IC25") (pin "6") (pinfunction "P2_6") (pintype "bidirectional"))
      (node (ref "R110") (pin "1") (pinfunction "1_1") (pintype "passive"))
      (node (ref "R117") (pin "2") (pinfunction "2_2") (pintype "passive"))
      (node (ref "SW6") (pin "3") (pinfunction "3_3") (pintype "passive"))
    )
    (net (code "12") (name "/DIR_CTRL11") (class "Default")
      (node (ref "IC25") (pin "7") (pinfunction "P3_7") (pintype "bidirectional"))
      (node (ref "R112") (pin "1") (pinfunction "1_1") (pintype "passive"))
      (node (ref "R119") (pin "2") (pinfunction "2_2") (pintype "passive"))
      (node (ref "SW6") (pin "4") (pinfunction "4_4") (pintype "passive"))
    )
    (net (code "13") (name "/DIR_CTRL12") (class "Default")
      (node (ref "IC25") (pin "9") (pinfunction "P4_9") (pintype "bidirectional"))
      (node (ref "R105") (pin "2") (pinfunction "2_2") (pintype "passive"))
      (node (ref "R114") (pin "1") (pinfunction "1_1") (pintype "passive"))
      (node (ref "SW6") (pin "5") (pinfunction "5_5") (pintype "passive"))
    )
    (net (code "14") (name "/DIR_CTRL13") (class "Default")
      (node (ref "IC25") (pin "10") (pinfunction "P5_10") (pintype "bidirectional"))
      (node (ref "R107") (pin "2") (pinfunction "2_2") (pintype "passive"))
      (node (ref "R116") (pin "1") (pinfunction "1_1") (pintype "passive"))
      (node (ref "SW6") (pin "6") (pinfunction "6_6") (pintype "passive"))
    )
    (net (code "15") (name "/DIR_CTRL14") (class "Default")
      (node (ref "IC25") (pin "11") (pinfunction "P6_11") (pintype "bidirectional"))
      (node (ref "R109") (pin "2") (pinfunction "2_2") (pintype "passive"))
      (node (ref "R118") (pin "1") (pinfunction "1_1") (pintype "passive"))
      (node (ref "SW6") (pin "7") (pinfunction "7_7") (pintype "passive"))
    )
    (net (code "16") (name "/DIR_CTRL15") (class "Default")
      (node (ref "IC25") (pin "12") (pinfunction "P7_12") (pintype "bidirectional"))
      (node (ref "R111") (pin "2") (pinfunction "2_2") (pintype "passive"))
      (node (ref "R120") (pin "1") (pinfunction "1_1") (pintype "passive"))
      (node (ref "SW6") (pin "8") (pinfunction "8_8") (pintype "passive"))
    )
    (net (code "17") (name "/I2C1_SCL") (class "Default")
      (node (ref "B2") (pin "1") (pinfunction "1_1") (pintype "bidirectional"))
      (node (ref "D9") (pin "6") (pinfunction "I/O4_6") (pintype "bidirectional"))
      (node (ref "IC23") (pin "14") (pinfunction "SCL_14") (pintype "input"))
      (node (ref "IC24") (pin "1") (pinfunction "SCL_1") (pintype "input"))
      (node (ref "J14") (pin "27") (pinfunction "27_27") (pintype "bidirectional"))
    )
    (net (code "18") (name "/I2C1_SDA") (class "Default")
      (node (ref "B1") (pin "1") (pinfunction "1_1") (pintype "bidirectional"))
      (node (ref "D9") (pin "1") (pinfunction "I/O1_1") (pintype "bidirectional"))
      (node (ref "IC23") (pin "15") (pinfunction "SDA_15") (pintype "bidirectional"))
      (node (ref "IC24") (pin "3") (pinfunction "SDA_3") (pintype "bidirectional"))
      (node (ref "J14") (pin "26") (pinfunction "26_26") (pintype "bidirectional"))
    )
    (net (code "19") (name "/I2C2_SCL") (class "Default")
      (node (ref "B4") (pin "1") (pinfunction "1_1") (pintype "bidirectional"))
      (node (ref "D10") (pin "6") (pinfunction "I/O4_6") (pintype "bidirectional"))
      (node (ref "IC25") (pin "14") (pinfunction "SCL_14") (pintype "input"))
      (node (ref "IC26") (pin "1") (pinfunction "SCL_1") (pintype "input"))
      (node (ref "J24") (pin "27") (pinfunction "27_27") (pintype "bidirectional"))
    )
    (net (code "20") (name "/I2C2_SDA") (class "Default")
      (node (ref "B3") (pin "1") (pinfunction "1_1") (pintype "bidirectional"))
      (node (ref "D10") (pin "1") (pinfunction "I/O1_1") (pintype "bidirectional"))
      (node (ref "IC25") (pin "15") (pinfunction "SDA_15") (pintype "bidirectional"))
      (node (ref "IC26") (pin "3") (pinfunction "SDA_3") (pintype "bidirectional"))
      (node (ref "J24") (pin "26") (pinfunction "26_26") (pintype "bidirectional"))
    )
    (net (code "21") (name "/LVDS0_N") (class "Default")
      (node (ref "J14") (pin "3") (pinfunction "3_3") (pintype "bidirectional"))
    )
    (net (code "22") (name "/LVDS0_P") (class "Default")
      (node (ref "J14") (pin "2") (pinfunction "2_2") (pintype "bidirectional"))
    )
    (net (code "23") (name "/LVDS1_N") (class "Default")
      (node (ref "J14") (pin "6") (pinfunction "6_6") (pintype "bidirectional"))
    )
    (net (code "24") (name "/LVDS1_P") (class "Default")
      (node (ref "J14") (pin "5") (pinfunction "5_5") (pintype "bidirectional"))
    )
    (net (code "25") (name "/LVDS2_N") (class "Default")
      (node (ref "J14") (pin "9") (pinfunction "9_9") (pintype "bidirectional"))
    )
    (net (code "26") (name "/LVDS2_P") (class "Default")
      (node (ref "J14") (pin "8") (pinfunction "8_8") (pintype "bidirectional"))
    )
    (net (code "27") (name "/LVDS3_N") (class "Default")
      (node (ref "J14") (pin "12") (pinfunction "12_12") (pintype "bidirectional"))
    )
    (net (code "28") (name "/LVDS3_P") (class "Default")
      (node (ref "J14") (pin "11") (pinfunction "11_11") (pintype "bidirectional"))
    )
    (net (code "29") (name "/LVDS4_N") (class "Default")
      (node (ref "J14") (pin "15") (pinfunction "15_15") (pintype "bidirectional"))
    )
    (net (code "30") (name "/LVDS4_P") (class "Default")
      (node (ref "J14") (pin "14") (pinfunction "14_14") (pintype "bidirectional"))
    )
    (net (code "31") (name "/LVDS5_N") (class "Default")
      (node (ref "J14") (pin "18") (pinfunction "18_18") (pintype "bidirectional"))
    )
    (net (code "32") (name "/LVDS5_P") (class "Default")
      (node (ref "J14") (pin "17") (pinfunction "17_17") (pintype "bidirectional"))
    )
    (net (code "33") (name "/LVDS6_N") (class "Default")
      (node (ref "J14") (pin "21") (pinfunction "21_21") (pintype "bidirectional"))
    )
    (net (code "34") (name "/LVDS6_P") (class "Default")
      (node (ref "J14") (pin "20") (pinfunction "20_20") (pintype "bidirectional"))
    )
    (net (code "35") (name "/LVDS7_N") (class "Default")
      (node (ref "J14") (pin "24") (pinfunction "24_24") (pintype "bidirectional"))
    )
    (net (code "36") (name "/LVDS7_P") (class "Default")
      (node (ref "J14") (pin "23") (pinfunction "23_23") (pintype "bidirectional"))
    )
    (net (code "37") (name "/LVDS8_N") (class "Default")
      (node (ref "J24") (pin "3") (pinfunction "3_3") (pintype "bidirectional"))
    )
    (net (code "38") (name "/LVDS8_P") (class "Default")
      (node (ref "J24") (pin "2") (pinfunction "2_2") (pintype "bidirectional"))
    )
    (net (code "39") (name "/LVDS9_N") (class "Default")
      (node (ref "J24") (pin "6") (pinfunction "6_6") (pintype "bidirectional"))
    )
    (net (code "40") (name "/LVDS9_P") (class "Default")
      (node (ref "J24") (pin "5") (pinfunction "5_5") (pintype "bidirectional"))
    )
    (net (code "41") (name "/LVDS10_N") (class "Default")
      (node (ref "J24") (pin "9") (pinfunction "9_9") (pintype "bidirectional"))
    )
    (net (code "42") (name "/LVDS10_P") (class "Default")
      (node (ref "J24") (pin "8") (pinfunction "8_8") (pintype "bidirectional"))
    )
    (net (code "43") (name "/LVDS11_N") (class "Default")
      (node (ref "J24") (pin "12") (pinfunction "12_12") (pintype "bidirectional"))
    )
    (net (code "44") (name "/LVDS11_P") (class "Default")
      (node (ref "J24") (pin "11") (pinfunction "11_11") (pintype "bidirectional"))
    )
    (net (code "45") (name "/LVDS12_N") (class "Default")
      (node (ref "J24") (pin "15") (pinfunction "15_15") (pintype "bidirectional"))
    )
    (net (code "46") (name "/LVDS12_P") (class "Default")
      (node (ref "J24") (pin "14") (pinfunction "14_14") (pintype "bidirectional"))
    )
    (net (code "47") (name "/LVDS13_N") (class "Default")
      (node (ref "J24") (pin "18") (pinfunction "18_18") (pintype "bidirectional"))
    )
    (net (code "48") (name "/LVDS13_P") (class "Default")
      (node (ref "J24") (pin "17") (pinfunction "17_17") (pintype "bidirectional"))
    )
    (net (code "49") (name "/LVDS14_N") (class "Default")
      (node (ref "J24") (pin "21") (pinfunction "21_21") (pintype "bidirectional"))
    )
    (net (code "50") (name "/LVDS14_P") (class "Default")
      (node (ref "J24") (pin "20") (pinfunction "20_20") (pintype "bidirectional"))
    )
    (net (code "51") (name "/LVDS15_N") (class "Default")
      (node (ref "J24") (pin "24") (pinfunction "24_24") (pintype "bidirectional"))
    )
    (net (code "52") (name "/LVDS15_P") (class "Default")
      (node (ref "J24") (pin "23") (pinfunction "23_23") (pintype "bidirectional"))
    )
    (net (code "53") (name "/LVDSC0_N") (class "Default")
      (node (ref "D1") (pin "3") (pinfunction "I/O2_3") (pintype "bidirectional"))
      (node (ref "J15") (pin "2D") (pinfunction "2_2D") (pintype "bidirectional"))
    )
    (net (code "54") (name "/LVDSC0_P") (class "Default")
      (node (ref "D1") (pin "1") (pinfunction "I/O1_1") (pintype "bidirectional"))
      (node (ref "J15") (pin "1D") (pinfunction "1_1D") (pintype "bidirectional"))
    )
    (net (code "55") (name "/LVDSC1_N") (class "Default")
      (node (ref "D2") (pin "3") (pinfunction "I/O2_3") (pintype "bidirectional"))
      (node (ref "J15") (pin "5D") (pinfunction "5_5D") (pintype "bidirectional"))
    )
    (net (code "56") (name "/LVDSC1_P") (class "Default")
      (node (ref "D2") (pin "1") (pinfunction "I/O1_1") (pintype "bidirectional"))
      (node (ref "J15") (pin "4D") (pinfunction "4_4D") (pintype "bidirectional"))
    )
    (net (code "57") (name "/LVDSC2_N") (class "Default")
      (node (ref "D1") (pin "4") (pinfunction "I/O3_4") (pintype "bidirectional"))
      (node (ref "J15") (pin "6D") (pinfunction "6_6D") (pintype "bidirectional"))
    )
    (net (code "58") (name "/LVDSC2_P") (class "Default")
      (node (ref "D1") (pin "6") (pinfunction "I/O4_6") (pintype "bidirectional"))
      (node (ref "J15") (pin "3D") (pinfunction "3_3D") (pintype "bidirectional"))
    )
    (net (code "59") (name "/LVDSC3_N") (class "Default")
      (node (ref "D2") (pin "4") (pinfunction "I/O3_4") (pintype "bidirectional"))
      (node (ref "J15") (pin "8D") (pinfunction "8_8D") (pintype "bidirectional"))
    )
    (net (code "60") (name "/LVDSC3_P") (class "Default")
      (node (ref "D2") (pin "6") (pinfunction "I/O4_6") (pintype "bidirectional"))
      (node (ref "J15") (pin "7D") (pinfunction "7_7D") (pintype "bidirectional"))
    )
    (net (code "61") (name "/LVDSC4_N") (class "Default")
      (node (ref "D3") (pin "1") (pinfunction "I/O1_1") (pintype "bidirectional"))
      (node (ref "J15") (pin "2C") (pinfunction "2_2C") (pintype "bidirectional"))
    )
    (net (code "62") (name "/LVDSC4_P") (class "Default")
      (node (ref "D3") (pin "3") (pinfunction "I/O2_3") (pintype "bidirectional"))
      (node (ref "J15") (pin "1C") (pinfunction "1_1C") (pintype "bidirectional"))
    )
    (net (code "63") (name "/LVDSC5_N") (class "Default")
      (node (ref "D4") (pin "1") (pinfunction "I/O1_1") (pintype "bidirectional"))
      (node (ref "J15") (pin "5C") (pinfunction "5_5C") (pintype "bidirectional"))
    )
    (net (code "64") (name "/LVDSC5_P") (class "Default")
      (node (ref "D4") (pin "3") (pinfunction "I/O2_3") (pintype "bidirectional"))
      (node (ref "J15") (pin "4C") (pinfunction "4_4C") (pintype "bidirectional"))
    )
    (net (code "65") (name "/LVDSC6_N") (class "Default")
      (node (ref "D3") (pin "4") (pinfunction "I/O3_4") (pintype "bidirectional"))
      (node (ref "J15") (pin "6C") (pinfunction "6_6C") (pintype "bidirectional"))
    )
    (net (code "66") (name "/LVDSC6_P") (class "Default")
      (node (ref "D3") (pin "6") (pinfunction "I/O4_6") (pintype "bidirectional"))
      (node (ref "J15") (pin "3C") (pinfunction "3_3C") (pintype "bidirectional"))
    )
    (net (code "67") (name "/LVDSC7_N") (class "Default")
      (node (ref "D4") (pin "4") (pinfunction "I/O3_4") (pintype "bidirectional"))
      (node (ref "J15") (pin "8C") (pinfunction "8_8C") (pintype "bidirectional"))
    )
    (net (code "68") (name "/LVDSC7_P") (class "Default")
      (node (ref "D4") (pin "6") (pinfunction "I/O4_6") (pintype "bidirectional"))
      (node (ref "J15") (pin "7C") (pinfunction "7_7C") (pintype "bidirectional"))
    )
    (net (code "69") (name "/LVDSC8_N") (class "Default")
      (node (ref "D5") (pin "3") (pinfunction "I/O2_3") (pintype "bidirectional"))
      (node (ref "J15") (pin "2B") (pinfunction "2_2B") (pintype "bidirectional"))
    )
    (net (code "70") (name "/LVDSC8_P") (class "Default")
      (node (ref "D5") (pin "1") (pinfunction "I/O1_1") (pintype "bidirectional"))
      (node (ref "J15") (pin "1B") (pinfunction "1_1B") (pintype "bidirectional"))
    )
    (net (code "71") (name "/LVDSC9_N") (class "Default")
      (node (ref "D6") (pin "3") (pinfunction "I/O2_3") (pintype "bidirectional"))
      (node (ref "J15") (pin "5B") (pinfunction "5_5B") (pintype "bidirectional"))
    )
    (net (code "72") (name "/LVDSC9_P") (class "Default")
      (node (ref "D6") (pin "1") (pinfunction "I/O1_1") (pintype "bidirectional"))
      (node (ref "J15") (pin "4B") (pinfunction "4_4B") (pintype "bidirectional"))
    )
    (net (code "73") (name "/LVDSC10_N") (class "Default")
      (node (ref "D5") (pin "4") (pinfunction "I/O3_4") (pintype "bidirectional"))
      (node (ref "J15") (pin "6B") (pinfunction "6_6B") (pintype "bidirectional"))
    )
    (net (code "74") (name "/LVDSC10_P") (class "Default")
      (node (ref "D5") (pin "6") (pinfunction "I/O4_6") (pintype "bidirectional"))
      (node (ref "J15") (pin "3B") (pinfunction "3_3B") (pintype "bidirectional"))
    )
    (net (code "75") (name "/LVDSC11_N") (class "Default")
      (node (ref "D6") (pin "4") (pinfunction "I/O3_4") (pintype "bidirectional"))
      (node (ref "J15") (pin "8B") (pinfunction "8_8B") (pintype "bidirectional"))
    )
    (net (code "76") (name "/LVDSC11_P") (class "Default")
      (node (ref "D6") (pin "6") (pinfunction "I/O4_6") (pintype "bidirectional"))
      (node (ref "J15") (pin "7B") (pinfunction "7_7B") (pintype "bidirectional"))
    )
    (net (code "77") (name "/LVDSC12_N") (class "Default")
      (node (ref "D7") (pin "3") (pinfunction "I/O2_3") (pintype "bidirectional"))
      (node (ref "J15") (pin "2A") (pinfunction "2_2A") (pintype "bidirectional"))
    )
    (net (code "78") (name "/LVDSC12_P") (class "Default")
      (node (ref "D7") (pin "1") (pinfunction "I/O1_1") (pintype "bidirectional"))
      (node (ref "J15") (pin "1A") (pinfunction "1_1A") (pintype "bidirectional"))
    )
    (net (code "79") (name "/LVDSC13_N") (class "Default")
      (node (ref "D8") (pin "3") (pinfunction "I/O2_3") (pintype "bidirectional"))
      (node (ref "J15") (pin "5A") (pinfunction "5_5A") (pintype "bidirectional"))
    )
    (net (code "80") (name "/LVDSC13_P") (class "Default")
      (node (ref "D8") (pin "1") (pinfunction "I/O1_1") (pintype "bidirectional"))
      (node (ref "J15") (pin "4A") (pinfunction "4_4A") (pintype "bidirectional"))
    )
    (net (code "81") (name "/LVDSC14_N") (class "Default")
      (node (ref "D7") (pin "4") (pinfunction "I/O3_4") (pintype "bidirectional"))
      (node (ref "J15") (pin "6A") (pinfunction "6_6A") (pintype "bidirectional"))
    )
    (net (code "82") (name "/LVDSC14_P") (class "Default")
      (node (ref "D7") (pin "6") (pinfunction "I/O4_6") (pintype "bidirectional"))
      (node (ref "J15") (pin "3A") (pinfunction "3_3A") (pintype "bidirectional"))
    )
    (net (code "83") (name "/LVDSC15_N") (class "Default")
      (node (ref "D8") (pin "4") (pinfunction "I/O3_4") (pintype "bidirectional"))
      (node (ref "J15") (pin "8A") (pinfunction "8_8A") (pintype "bidirectional"))
    )
    (net (code "84") (name "/LVDSC15_P") (class "Default")
      (node (ref "D8") (pin "6") (pinfunction "I/O4_6") (pintype "bidirectional"))
      (node (ref "J15") (pin "7A") (pinfunction "7_7A") (pintype "bidirectional"))
    )
    (net (code "85") (name "GND") (class "Default")
      (node (ref "B5") (pin "1") (pinfunction "1_1") (pintype "bidirectional"))
      (node (ref "B7") (pin "1") (pinfunction "1_1") (pintype "bidirectional"))
      (node (ref "B9") (pin "1") (pinfunction "1_1") (pintype "bidirectional"))
      (node (ref "C1") (pin "2") (pinfunction "2_2") (pintype "passive"))
      (node (ref "C2") (pin "2") (pinfunction "2_2") (pintype "passive"))
      (node (ref "C57") (pin "1") (pinfunction "1_1") (pintype "passive"))
      (node (ref "C58") (pin "1") (pinfunction "1_1") (pintype "passive"))
      (node (ref "C59") (pin "1") (pinfunction "1_1") (pintype "passive"))
      (node (ref "C60") (pin "1") (pinfunction "1_1") (pintype "passive"))
      (node (ref "C61") (pin "1") (pinfunction "1_1") (pintype "passive"))
      (node (ref "C62") (pin "2") (pinfunction "2_2") (pintype "passive"))
      (node (ref "C63") (pin "1") (pinfunction "1_1") (pintype "passive"))
      (node (ref "C64") (pin "1") (pinfunction "1_1") (pintype "passive"))
      (node (ref "C65") (pin "1") (pinfunction "1_1") (pintype "passive"))
      (node (ref "C66") (pin "1") (pinfunction "1_1") (pintype "passive"))
      (node (ref "C67") (pin "1") (pinfunction "1_1") (pintype "passive"))
      (node (ref "C68") (pin "1") (pinfunction "1_1") (pintype "passive"))
      (node (ref "D1") (pin "2") (pinfunction "GND_2") (pintype "power_in"))
      (node (ref "D10") (pin "2") (pinfunction "GND_2") (pintype "power_in"))
      (node (ref "D2") (pin "2") (pinfunction "GND_2") (pintype "power_in"))
      (node (ref "D3") (pin "2") (pinfunction "GND_2") (pintype "power_in"))
      (node (ref "D4") (pin "2") (pinfunction "GND_2") (pintype "power_in"))
      (node (ref "D5") (pin "2") (pinfunction "GND_2") (pintype "power_in"))
      (node (ref "D6") (pin "2") (pinfunction "GND_2") (pintype "power_in"))
      (node (ref "D7") (pin "2") (pinfunction "GND_2") (pintype "power_in"))
      (node (ref "D8") (pin "2") (pinfunction "GND_2") (pintype "power_in"))
      (node (ref "D9") (pin "2") (pinfunction "GND_2") (pintype "power_in"))
      (node (ref "IC23") (pin "1") (pinfunction "A0_1") (pintype "input"))
      (node (ref "IC23") (pin "8") (pinfunction "GND_8") (pintype "power_in"))
      (node (ref "IC24") (pin "2") (pinfunction "VSS_2") (pintype "power_in"))
      (node (ref "IC25") (pin "1") (pinfunction "A0_1") (pintype "input"))
      (node (ref "IC25") (pin "8") (pinfunction "GND_8") (pintype "power_in"))
      (node (ref "IC26") (pin "2") (pinfunction "VSS_2") (pintype "power_in"))
      (node (ref "IC27") (pin "1") (pinfunction "PGND_1") (pintype "power_in"))
      (node (ref "IC27") (pin "11") (pinfunction "EP_11") (pintype "power_in"))
      (node (ref "IC27") (pin "6") (pinfunction "AGND_6") (pintype "power_in"))
      (node (ref "J14") (pin "1") (pinfunction "1_1") (pintype "bidirectional"))
      (node (ref "J14") (pin "10") (pinfunction "10_10") (pintype "bidirectional"))
      (node (ref "J14") (pin "13") (pinfunction "13_13") (pintype "bidirectional"))
      (node (ref "J14") (pin "16") (pinfunction "16_16") (pintype "bidirectional"))
      (node (ref "J14") (pin "19") (pinfunction "19_19") (pintype "bidirectional"))
      (node (ref "J14") (pin "22") (pinfunction "22_22") (pintype "bidirectional"))
      (node (ref "J14") (pin "25") (pinfunction "25_25") (pintype "bidirectional"))
      (node (ref "J14") (pin "4") (pinfunction "4_4") (pintype "bidirectional"))
      (node (ref "J14") (pin "7") (pinfunction "7_7") (pintype "bidirectional"))
      (node (ref "J15") (pin "SH") (pinfunction "1_SH") (pintype "passive"))
      (node (ref "J24") (pin "1") (pinfunction "1_1") (pintype "bidirectional"))
      (node (ref "J24") (pin "10") (pinfunction "10_10") (pintype "bidirectional"))
      (node (ref "J24") (pin "13") (pinfunction "13_13") (pintype "bidirectional"))
      (node (ref "J24") (pin "16") (pinfunction "16_16") (pintype "bidirectional"))
      (node (ref "J24") (pin "19") (pinfunction "19_19") (pintype "bidirectional"))
      (node (ref "J24") (pin "22") (pinfunction "22_22") (pintype "bidirectional"))
      (node (ref "J24") (pin "25") (pinfunction "25_25") (pintype "bidirectional"))
      (node (ref "J24") (pin "4") (pinfunction "4_4") (pintype "bidirectional"))
      (node (ref "J24") (pin "7") (pinfunction "7_7") (pintype "bidirectional"))
      (node (ref "LD5") (pin "1") (pinfunction "C_1") (pintype "passive"))
      (node (ref "LD6") (pin "1") (pinfunction "C_1") (pintype "passive"))
      (node (ref "LD7") (pin "1") (pinfunction "C_1") (pintype "passive"))
      (node (ref "LD8") (pin "1") (pinfunction "C_1") (pintype "passive"))
      (node (ref "R122") (pin "1") (pinfunction "1_1") (pintype "passive"))
      (node (ref "R8") (pin "1") (pinfunction "1_1") (pintype "passive"))
      (node (ref "R9") (pin "1") (pinfunction "1_1") (pintype "passive"))
      (node (ref "SW5") (pin "10") (pinfunction "10_10") (pintype "passive"))
      (node (ref "SW5") (pin "11") (pinfunction "11_11") (pintype "passive"))
      (node (ref "SW5") (pin "12") (pinfunction "12_12") (pintype "passive"))
      (node (ref "SW5") (pin "13") (pinfunction "13_13") (pintype "passive"))
      (node (ref "SW5") (pin "14") (pinfunction "14_14") (pintype "passive"))
      (node (ref "SW5") (pin "15") (pinfunction "15_15") (pintype "passive"))
      (node (ref "SW5") (pin "16") (pinfunction "16_16") (pintype "passive"))
      (node (ref "SW5") (pin "9") (pinfunction "9_9") (pintype "passive"))
      (node (ref "SW6") (pin "10") (pinfunction "10_10") (pintype "passive"))
      (node (ref "SW6") (pin "11") (pinfunction "11_11") (pintype "passive"))
      (node (ref "SW6") (pin "12") (pinfunction "12_12") (pintype "passive"))
      (node (ref "SW6") (pin "13") (pinfunction "13_13") (pintype "passive"))
      (node (ref "SW6") (pin "14") (pinfunction "14_14") (pintype "passive"))
      (node (ref "SW6") (pin "15") (pinfunction "15_15") (pintype "passive"))
      (node (ref "SW6") (pin "16") (pinfunction "16_16") (pintype "passive"))
      (node (ref "SW6") (pin "9") (pinfunction "9_9") (pintype "passive"))
    )
    (net (code "86") (name "Net-(B12-Pad1)") (class "Default")
      (node (ref "B12") (pin "1") (pinfunction "1_1") (pintype "bidirectional"))
      (node (ref "C1") (pin "1") (pinfunction "1_1") (pintype "passive"))
      (node (ref "R8") (pin "2") (pinfunction "2_2") (pintype "passive"))
    )
    (net (code "87") (name "Net-(B13-Pad1)") (class "Default")
      (node (ref "B13") (pin "1") (pinfunction "1_1") (pintype "bidirectional"))
      (node (ref "C2") (pin "1") (pinfunction "1_1") (pintype "passive"))
      (node (ref "R9") (pin "2") (pinfunction "2_2") (pintype "passive"))
    )
    (net (code "88") (name "Net-(IC27-FB)") (class "Default")
      (node (ref "IC27") (pin "5") (pinfunction "FB_5") (pintype "input"))
      (node (ref "R121") (pin "1") (pinfunction "1_1") (pintype "passive"))
      (node (ref "R122") (pin "2") (pinfunction "2_2") (pintype "passive"))
    )
    (net (code "89") (name "Net-(IC27-SW)") (class "Default")
      (node (ref "IC27") (pin "9") (pinfunction "SW_9") (pintype "output"))
      (node (ref "L2") (pin "1") (pinfunction "1_1") (pintype "passive"))
    )
    (net (code "90") (name "Net-(LD1A-C)") (class "Default")
      (node (ref "LD1") (pin "1") (pinfunction "C_1") (pintype "passive"))
      (node (ref "R89") (pin "1") (pinfunction "1_1") (pintype "passive"))
    )
    (net (code "91") (name "Net-(LD1B-C)") (class "Default")
      (node (ref "LD1") (pin "3") (pinfunction "C_3") (pintype "passive"))
      (node (ref "R91") (pin "1") (pinfunction "1_1") (pintype "passive"))
    )
    (net (code "92") (name "Net-(LD1C-C)") (class "Default")
      (node (ref "LD1") (pin "5") (pinfunction "C_5") (pintype "passive"))
      (node (ref "R93") (pin "1") (pinfunction "1_1") (pintype "passive"))
    )
    (net (code "93") (name "Net-(LD1D-C)") (class "Default")
      (node (ref "LD1") (pin "7") (pinfunction "C_7") (pintype "passive"))
      (node (ref "R95") (pin "1") (pinfunction "1_1") (pintype "passive"))
    )
    (net (code "94") (name "Net-(LD2A-C)") (class "Default")
      (node (ref "LD2") (pin "1") (pinfunction "C_1") (pintype "passive"))
      (node (ref "R97") (pin "1") (pinfunction "1_1") (pintype "passive"))
    )
    (net (code "95") (name "Net-(LD2B-C)") (class "Default")
      (node (ref "LD2") (pin "3") (pinfunction "C_3") (pintype "passive"))
      (node (ref "R99") (pin "1") (pinfunction "1_1") (pintype "passive"))
    )
    (net (code "96") (name "Net-(LD2C-C)") (class "Default")
      (node (ref "LD2") (pin "5") (pinfunction "C_5") (pintype "passive"))
      (node (ref "R101") (pin "1") (pinfunction "1_1") (pintype "passive"))
    )
    (net (code "97") (name "Net-(LD2D-C)") (class "Default")
      (node (ref "LD2") (pin "7") (pinfunction "C_7") (pintype "passive"))
      (node (ref "R103") (pin "1") (pinfunction "1_1") (pintype "passive"))
    )
    (net (code "98") (name "Net-(LD3A-C)") (class "Default")
      (node (ref "LD3") (pin "1") (pinfunction "C_1") (pintype "passive"))
      (node (ref "R105") (pin "1") (pinfunction "1_1") (pintype "passive"))
    )
    (net (code "99") (name "Net-(LD3B-C)") (class "Default")
      (node (ref "LD3") (pin "3") (pinfunction "C_3") (pintype "passive"))
      (node (ref "R107") (pin "1") (pinfunction "1_1") (pintype "passive"))
    )
    (net (code "100") (name "Net-(LD3C-C)") (class "Default")
      (node (ref "LD3") (pin "5") (pinfunction "C_5") (pintype "passive"))
      (node (ref "R109") (pin "1") (pinfunction "1_1") (pintype "passive"))
    )
    (net (code "101") (name "Net-(LD3D-C)") (class "Default")
      (node (ref "LD3") (pin "7") (pinfunction "C_7") (pintype "passive"))
      (node (ref "R111") (pin "1") (pinfunction "1_1") (pintype "passive"))
    )
    (net (code "102") (name "Net-(LD4A-C)") (class "Default")
      (node (ref "LD4") (pin "1") (pinfunction "C_1") (pintype "passive"))
      (node (ref "R113") (pin "1") (pinfunction "1_1") (pintype "passive"))
    )
    (net (code "103") (name "Net-(LD4B-C)") (class "Default")
      (node (ref "LD4") (pin "3") (pinfunction "C_3") (pintype "passive"))
      (node (ref "R115") (pin "1") (pinfunction "1_1") (pintype "passive"))
    )
    (net (code "104") (name "Net-(LD4C-C)") (class "Default")
      (node (ref "LD4") (pin "5") (pinfunction "C_5") (pintype "passive"))
      (node (ref "R117") (pin "1") (pinfunction "1_1") (pintype "passive"))
    )
    (net (code "105") (name "Net-(LD4D-C)") (class "Default")
      (node (ref "LD4") (pin "7") (pinfunction "C_7") (pintype "passive"))
      (node (ref "R119") (pin "1") (pinfunction "1_1") (pintype "passive"))
    )
    (net (code "106") (name "Net-(LD5-A)") (class "Default")
      (node (ref "LD5") (pin "2") (pinfunction "A_2") (pintype "passive"))
      (node (ref "R1") (pin "1") (pinfunction "1_1") (pintype "passive"))
    )
    (net (code "107") (name "Net-(LD6-A)") (class "Default")
      (node (ref "LD6") (pin "2") (pinfunction "A_2") (pintype "passive"))
      (node (ref "R3") (pin "2") (pinfunction "2_2") (pintype "passive"))
    )
    (net (code "108") (name "Net-(LD7-A)") (class "Default")
      (node (ref "LD7") (pin "2") (pinfunction "A_2") (pintype "passive"))
      (node (ref "R5") (pin "2") (pinfunction "2_2") (pintype "passive"))
    )
    (net (code "109") (name "Net-(LD8-A)") (class "Default")
      (node (ref "LD8") (pin "2") (pinfunction "A_2") (pintype "passive"))
      (node (ref "R7") (pin "2") (pinfunction "2_2") (pintype "passive"))
    )
    (net (code "110") (name "Net-(R2-Pad2)") (class "Default")
      (node (ref "R2") (pin "2") (pinfunction "2_2") (pintype "passive"))
      (node (ref "R3") (pin "1") (pinfunction "1_1") (pintype "passive"))
    )
    (net (code "111") (name "Net-(R4-Pad2)") (class "Default")
      (node (ref "R4") (pin "2") (pinfunction "2_2") (pintype "passive"))
      (node (ref "R5") (pin "1") (pinfunction "1_1") (pintype "passive"))
    )
    (net (code "112") (name "Net-(R6-Pad2)") (class "Default")
      (node (ref "R6") (pin "2") (pinfunction "2_2") (pintype "passive"))
      (node (ref "R7") (pin "1") (pinfunction "1_1") (pintype "passive"))
    )
    (net (code "113") (name "P3V3") (class "Default")
      (node (ref "B10") (pin "1") (pinfunction "1_1") (pintype "bidirectional"))
      (node (ref "C59") (pin "2") (pinfunction "2_2") (pintype "passive"))
      (node (ref "C60") (pin "2") (pinfunction "2_2") (pintype "passive"))
      (node (ref "C61") (pin "2") (pinfunction "2_2") (pintype "passive"))
      (node (ref "C62") (pin "1") (pinfunction "1_1") (pintype "passive"))
      (node (ref "C65") (pin "2") (pinfunction "2_2") (pintype "passive"))
      (node (ref "C66") (pin "2") (pinfunction "2_2") (pintype "passive"))
      (node (ref "D1") (pin "5") (pinfunction "VBUS_5") (pintype "power_in"))
      (node (ref "D2") (pin "5") (pinfunction "VBUS_5") (pintype "power_in"))
      (node (ref "D3") (pin "5") (pinfunction "VBUS_5") (pintype "power_in"))
      (node (ref "D4") (pin "5") (pinfunction "VBUS_5") (pintype "power_in"))
      (node (ref "D5") (pin "5") (pinfunction "VBUS_5") (pintype "power_in"))
      (node (ref "D6") (pin "5") (pinfunction "VBUS_5") (pintype "power_in"))
      (node (ref "D7") (pin "5") (pinfunction "VBUS_5") (pintype "power_in"))
      (node (ref "D8") (pin "5") (pinfunction "VBUS_5") (pintype "power_in"))
      (node (ref "IC27") (pin "10") (pinfunction "VOS_10") (pintype "input"))
      (node (ref "IC27") (pin "8") (pinfunction "SLEEP_8") (pintype "input"))
      (node (ref "L2") (pin "2") (pinfunction "2_2") (pintype "passive"))
      (node (ref "LD1") (pin "2") (pinfunction "A_2") (pintype "passive"))
      (node (ref "LD1") (pin "4") (pinfunction "A_4") (pintype "passive"))
      (node (ref "LD1") (pin "6") (pinfunction "A_6") (pintype "passive"))
      (node (ref "LD1") (pin "8") (pinfunction "A_8") (pintype "passive"))
      (node (ref "LD2") (pin "2") (pinfunction "A_2") (pintype "passive"))
      (node (ref "LD2") (pin "4") (pinfunction "A_4") (pintype "passive"))
      (node (ref "LD2") (pin "6") (pinfunction "A_6") (pintype "passive"))
      (node (ref "LD2") (pin "8") (pinfunction "A_8") (pintype "passive"))
      (node (ref "LD3") (pin "2") (pinfunction "A_2") (pintype "passive"))
      (node (ref "LD3") (pin "4") (pinfunction "A_4") (pintype "passive"))
      (node (ref "LD3") (pin "6") (pinfunction "A_6") (pintype "passive"))
      (node (ref "LD3") (pin "8") (pinfunction "A_8") (pintype "passive"))
      (node (ref "LD4") (pin "2") (pinfunction "A_2") (pintype "passive"))
      (node (ref "LD4") (pin "4") (pinfunction "A_4") (pintype "passive"))
      (node (ref "LD4") (pin "6") (pinfunction "A_6") (pintype "passive"))
      (node (ref "LD4") (pin "8") (pinfunction "A_8") (pintype "passive"))
      (node (ref "R100") (pin "2") (pinfunction "2_2") (pintype "passive"))
      (node (ref "R102") (pin "2") (pinfunction "2_2") (pintype "passive"))
      (node (ref "R104") (pin "2") (pinfunction "2_2") (pintype "passive"))
      (node (ref "R106") (pin "2") (pinfunction "2_2") (pintype "passive"))
      (node (ref "R108") (pin "2") (pinfunction "2_2") (pintype "passive"))
      (node (ref "R110") (pin "2") (pinfunction "2_2") (pintype "passive"))
      (node (ref "R112") (pin "2") (pinfunction "2_2") (pintype "passive"))
      (node (ref "R114") (pin "2") (pinfunction "2_2") (pintype "passive"))
      (node (ref "R116") (pin "2") (pinfunction "2_2") (pintype "passive"))
      (node (ref "R118") (pin "2") (pinfunction "2_2") (pintype "passive"))
      (node (ref "R120") (pin "2") (pinfunction "2_2") (pintype "passive"))
      (node (ref "R121") (pin "2") (pinfunction "2_2") (pintype "passive"))
      (node (ref "R2") (pin "1") (pinfunction "1_1") (pintype "passive"))
      (node (ref "R90") (pin "2") (pinfunction "2_2") (pintype "passive"))
      (node (ref "R92") (pin "2") (pinfunction "2_2") (pintype "passive"))
      (node (ref "R94") (pin "2") (pinfunction "2_2") (pintype "passive"))
      (node (ref "R96") (pin "2") (pinfunction "2_2") (pintype "passive"))
      (node (ref "R98") (pin "2") (pinfunction "2_2") (pintype "passive"))
    )
    (net (code "114") (name "P3V3_MP1") (class "Default")
      (node (ref "B8") (pin "1") (pinfunction "1_1") (pintype "bidirectional"))
      (node (ref "C57") (pin "2") (pinfunction "2_2") (pintype "passive"))
      (node (ref "C58") (pin "2") (pinfunction "2_2") (pintype "passive"))
      (node (ref "D9") (pin "5") (pinfunction "VBUS_5") (pintype "power_in"))
      (node (ref "IC23") (pin "16") (pinfunction "VCC_16") (pintype "bidirectional"))
      (node (ref "IC23") (pin "2") (pinfunction "A1_2") (pintype "input"))
      (node (ref "IC23") (pin "3") (pinfunction "A2_3") (pintype "input"))
      (node (ref "IC24") (pin "4") (pinfunction "VCC_4") (pintype "power_in"))
      (node (ref "J14") (pin "30") (pinfunction "30_30") (pintype "bidirectional"))
      (node (ref "R6") (pin "1") (pinfunction "1_1") (pintype "passive"))
    )
    (net (code "115") (name "P3V3_MP2") (class "Default")
      (node (ref "B6") (pin "1") (pinfunction "1_1") (pintype "bidirectional"))
      (node (ref "C63") (pin "2") (pinfunction "2_2") (pintype "passive"))
      (node (ref "C64") (pin "2") (pinfunction "2_2") (pintype "passive"))
      (node (ref "D10") (pin "5") (pinfunction "VBUS_5") (pintype "power_in"))
      (node (ref "IC25") (pin "16") (pinfunction "VCC_16") (pintype "bidirectional"))
      (node (ref "IC25") (pin "2") (pinfunction "A1_2") (pintype "input"))
      (node (ref "IC25") (pin "3") (pinfunction "A2_3") (pintype "input"))
      (node (ref "IC26") (pin "4") (pinfunction "VCC_4") (pintype "power_in"))
      (node (ref "J24") (pin "30") (pinfunction "30_30") (pintype "bidirectional"))
      (node (ref "R4") (pin "1") (pinfunction "1_1") (pintype "passive"))
    )
    (net (code "116") (name "P12V0") (class "Default")
      (node (ref "B11") (pin "1") (pinfunction "1_1") (pintype "bidirectional"))
      (node (ref "C67") (pin "2") (pinfunction "2_2") (pintype "passive"))
      (node (ref "C68") (pin "2") (pinfunction "2_2") (pintype "passive"))
      (node (ref "IC27") (pin "2") (pinfunction "VIN_2") (pintype "input"))
      (node (ref "IC27") (pin "3") (pinfunction "EN_3") (pintype "input"))
      (node (ref "J14") (pin "28") (pinfunction "28_28") (pintype "bidirectional"))
      (node (ref "J14") (pin "29") (pinfunction "29_29") (pintype "bidirectional"))
      (node (ref "J24") (pin "28") (pinfunction "28_28") (pintype "bidirectional"))
      (node (ref "J24") (pin "29") (pinfunction "29_29") (pintype "bidirectional"))
      (node (ref "R1") (pin "2") (pinfunction "2_2") (pintype "passive"))
    )
    (net (code "117") (name "unconnected-(D9-I{slash}O2-Pad3)") (class "Default")
      (node (ref "D9") (pin "3") (pinfunction "I/O2_3") (pintype "bidirectional"))
    )
    (net (code "118") (name "unconnected-(D9-I{slash}O3-Pad4)") (class "Default")
      (node (ref "D9") (pin "4") (pinfunction "I/O3_4") (pintype "bidirectional"))
    )
    (net (code "119") (name "unconnected-(D10-I{slash}O2-Pad3)") (class "Default")
      (node (ref "D10") (pin "3") (pinfunction "I/O2_3") (pintype "bidirectional"))
    )
    (net (code "120") (name "unconnected-(D10-I{slash}O3-Pad4)") (class "Default")
      (node (ref "D10") (pin "4") (pinfunction "I/O3_4") (pintype "bidirectional"))
    )
    (net (code "121") (name "unconnected-(IC23-~{INT}-Pad13)") (class "Default")
      (node (ref "IC23") (pin "13") (pinfunction "~{INT}_13") (pintype "output"))
    )
    (net (code "122") (name "unconnected-(IC24-NC-Pad5)") (class "Default")
      (node (ref "IC24") (pin "5") (pinfunction "NC_5") (pintype "passive"))
    )
    (net (code "123") (name "unconnected-(IC25-~{INT}-Pad13)") (class "Default")
      (node (ref "IC25") (pin "13") (pinfunction "~{INT}_13") (pintype "output"))
    )
    (net (code "124") (name "unconnected-(IC26-NC-Pad5)") (class "Default")
      (node (ref "IC26") (pin "5") (pinfunction "NC_5") (pintype "passive"))
    )
    (net (code "125") (name "unconnected-(IC27-NC-Pad4)") (class "Default")
      (node (ref "IC27") (pin "4") (pinfunction "NC_4") (pintype "passive"))
    )
    (net (code "126") (name "unconnected-(IC27-PG-Pad7)") (class "Default")
      (node (ref "IC27") (pin "7") (pinfunction "PG_7") (pintype "output"))
    )
  )
)
